# high_filter.net
KiCad netlist of a schematic drawn in Altium Designer
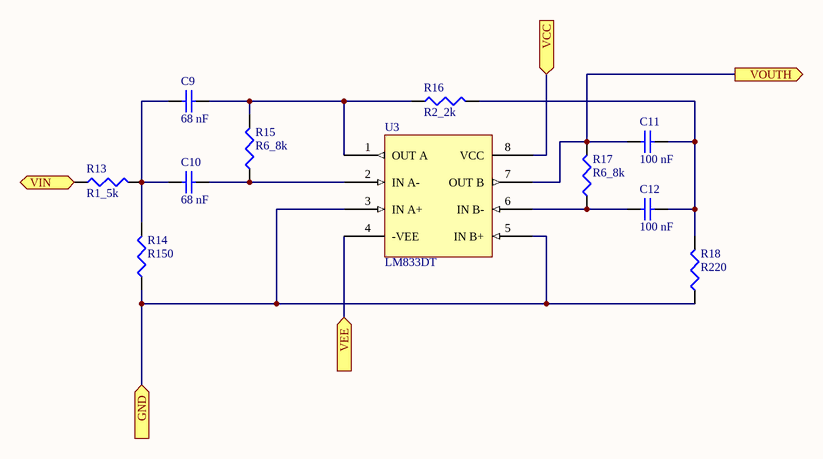
[diagram p0: high_filter.SchDoc]

(export (version "E")
  (design (tool "Eeschema 10.0.6"))
  (components
    (comp (ref "C9")
      (value "68 nF")
      (footprint "C0603")
      (description "68 nF Surface Mount Capacitor")
      (fields
        (field (name "MANUFACTURER") "Murata Electronics North America")
        (field (name "MANUFACTURER PART NUMBER") "GRM188R71E683KA01D")
      )
      (libsource (lib "Capstone Libraries") (part "C68nF"))
    )
    (comp (ref "C10")
      (value "68 nF")
      (footprint "C0603")
      (description "68 nF Surface Mount Capacitor")
      (fields
        (field (name "MANUFACTURER") "Murata Electronics North America")
        (field (name "MANUFACTURER PART NUMBER") "GRM188R71E683KA01D")
      )
      (libsource (lib "Capstone Libraries") (part "C68nF"))
    )
    (comp (ref "C11")
      (value "100 nF")
      (footprint "C0603")
      (description "100 nF Surface Mount Capacitor")
      (fields
        (field (name "MANUFACTURER") "Murata Electronics North America")
        (field (name "MANUFACTURER PART NUMBER") "GRM188R71C104KA01D")
      )
      (libsource (lib "Capstone Libraries") (part "C100nF"))
    )
    (comp (ref "C12")
      (value "100 nF")
      (footprint "C0603")
      (description "100 nF Surface Mount Capacitor")
      (fields
        (field (name "MANUFACTURER") "Murata Electronics North America")
        (field (name "MANUFACTURER PART NUMBER") "GRM188R71C104KA01D")
      )
      (libsource (lib "Capstone Libraries") (part "C100nF"))
    )
    (comp (ref "R13")
      (value "R1_5k")
      (footprint "R0603")
      (description "1.5k Ohms Surface Mount Resistor")
      (fields
        (field (name "MANUFACTURER") "Yageo")
        (field (name "MANUFACTURER PART NUMBER") "RC0603FR-071K5L")
      )
      (libsource (lib "Capstone Libraries") (part "R1_5k"))
    )
    (comp (ref "R14")
      (value "R150")
      (footprint "R0603")
      (description "150 Ohms Surface Mount Resistor")
      (fields
        (field (name "MANUFACTURER") "Yageo")
        (field (name "MANUFACTURER PART NUMBER") "RC0603FR-07150RL")
      )
      (libsource (lib "Capstone Libraries") (part "R150"))
    )
    (comp (ref "R15")
      (value "R6_8k")
      (footprint "R0603")
      (description "6.8k Ohms Surface Mount Resistor")
      (fields
        (field (name "MANUFACTURER") "Panasonic Electronic Components")
        (field (name "MANUFACTURER PART NUMBER") "ERJ-3EKF6801V")
      )
      (libsource (lib "Capstone Libraries") (part "R6_8k"))
    )
    (comp (ref "R16")
      (value "R2_2k")
      (footprint "R0603")
      (description "2.2k Ohms Surface Mount Resistor")
      (fields
        (field (name "MANUFACTURER") "Yageo")
        (field (name "MANUFACTURER PART NUMBER") "RC0603FR-072K2L")
      )
      (libsource (lib "Capstone Libraries") (part "R2_2k"))
    )
    (comp (ref "R17")
      (value "R6_8k")
      (footprint "R0603")
      (description "6.8k Ohms Surface Mount Resistor")
      (fields
        (field (name "MANUFACTURER") "Panasonic Electronic Components")
        (field (name "MANUFACTURER PART NUMBER") "ERJ-3EKF6801V")
      )
      (libsource (lib "Capstone Libraries") (part "R6_8k"))
    )
    (comp (ref "R18")
      (value "R220")
      (footprint "R0603")
      (description "220 Ohms Surface Mount Resistor")
      (fields
        (field (name "MANUFACTURER") "Yageo")
        (field (name "MANUFACTURER PART NUMBER") "RC0603FR-07220RL")
      )
      (libsource (lib "Capstone Libraries") (part "R220"))
    )
    (comp (ref "U3")
      (value "LM833DT")
      (footprint "soic8")
      (description "IC Dual Audio Amplifier")
      (fields (field (name "MANUFACTURER") "STMicroelectronics"))
      (libsource (lib "Capstone Libraries") (part "LM833DT"))
    )
  )
  (nets
    (net (code "1") (name "/GND") (class "Default")
      (node (ref "R14") (pin "1") (pinfunction "1_1") (pintype "passive"))
      (node (ref "R18") (pin "1") (pinfunction "1_1") (pintype "passive"))
      (node (ref "U3") (pin "3") (pinfunction "IN_A+_3") (pintype "input"))
      (node (ref "U3") (pin "5") (pinfunction "IN_B+_5") (pintype "input"))
    )
    (net (code "2") (name "/VCC") (class "Default")
      (node (ref "U3") (pin "8") (pinfunction "VCC_8") (pintype "passive"))
    )
    (net (code "3") (name "/VEE") (class "Default")
      (node (ref "U3") (pin "4") (pinfunction "-VEE_4") (pintype "passive"))
    )
    (net (code "4") (name "/VIN") (class "Default")
      (node (ref "R13") (pin "1") (pinfunction "1_1") (pintype "passive"))
    )
    (net (code "5") (name "/VOUTH") (class "Default")
      (node (ref "C11") (pin "1") (pinfunction "1_1") (pintype "passive"))
      (node (ref "R17") (pin "2") (pinfunction "2_2") (pintype "passive"))
      (node (ref "U3") (pin "7") (pinfunction "OUT_B_7") (pintype "output"))
    )
    (net (code "6") (name "Net-(C10-Pad1)") (class "Default")
      (node (ref "C10") (pin "1") (pinfunction "1_1") (pintype "passive"))
      (node (ref "C9") (pin "1") (pinfunction "1_1") (pintype "passive"))
      (node (ref "R13") (pin "2") (pinfunction "2_2") (pintype "passive"))
      (node (ref "R14") (pin "2") (pinfunction "2_2") (pintype "passive"))
    )
    (net (code "7") (name "Net-(C11-Pad2)") (class "Default")
      (node (ref "C11") (pin "2") (pinfunction "2_2") (pintype "passive"))
      (node (ref "C12") (pin "2") (pinfunction "2_2") (pintype "passive"))
      (node (ref "R16") (pin "2") (pinfunction "2_2") (pintype "passive"))
      (node (ref "R18") (pin "2") (pinfunction "2_2") (pintype "passive"))
    )
    (net (code "8") (name "Net-(U3-IN_A-)") (class "Default")
      (node (ref "C10") (pin "2") (pinfunction "2_2") (pintype "passive"))
      (node (ref "R15") (pin "1") (pinfunction "1_1") (pintype "passive"))
      (node (ref "U3") (pin "2") (pinfunction "IN_A-_2") (pintype "input"))
    )
    (net (code "9") (name "Net-(U3-IN_B-)") (class "Default")
      (node (ref "C12") (pin "1") (pinfunction "1_1") (pintype "passive"))
      (node (ref "R17") (pin "1") (pinfunction "1_1") (pintype "passive"))
      (node (ref "U3") (pin "6") (pinfunction "IN_B-_6") (pintype "input"))
    )
    (net (code "10") (name "Net-(U3-OUT_A)") (class "Default")
      (node (ref "C9") (pin "2") (pinfunction "2_2") (pintype "passive"))
      (node (ref "R15") (pin "2") (pinfunction "2_2") (pintype "passive"))
      (node (ref "R16") (pin "1") (pinfunction "1_1") (pintype "passive"))
      (node (ref "U3") (pin "1") (pinfunction "OUT_A_1") (pintype "output"))
    )
  )
)
